# csa_drvio_v1_1a.net
KiCad netlist of a schematic drawn in EAGLE
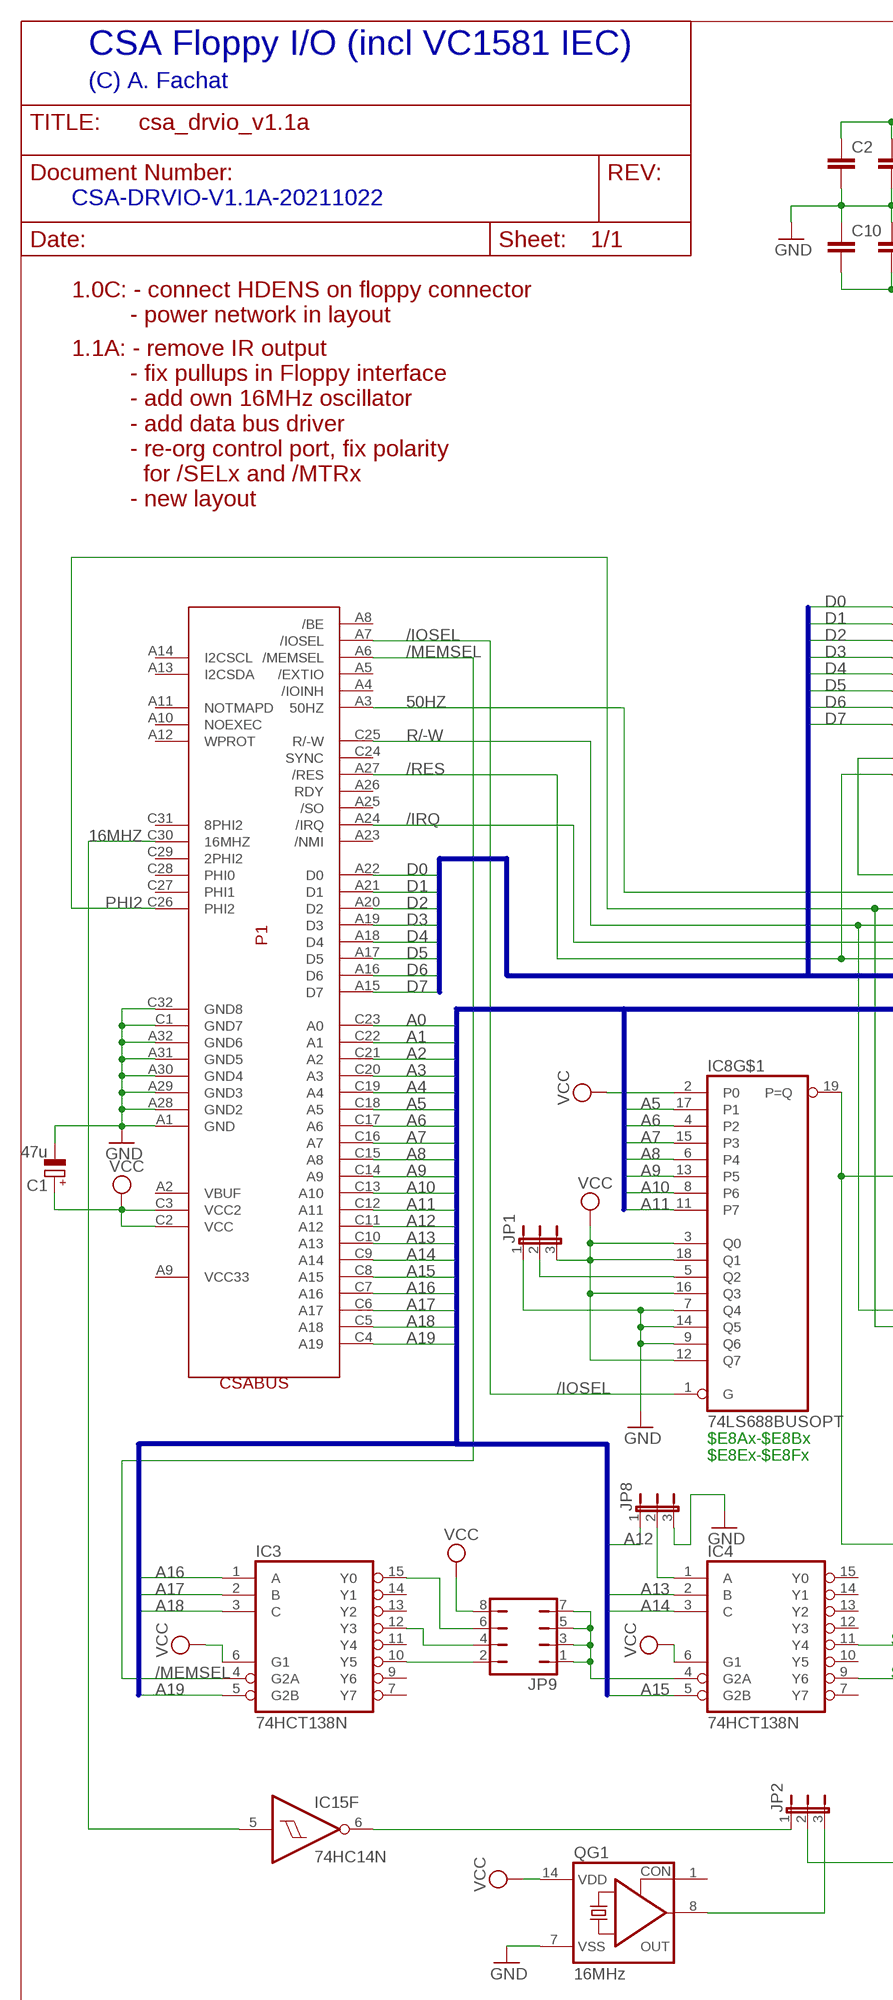
[diagram p0: schematic, sheet 1, part 1 of 2]
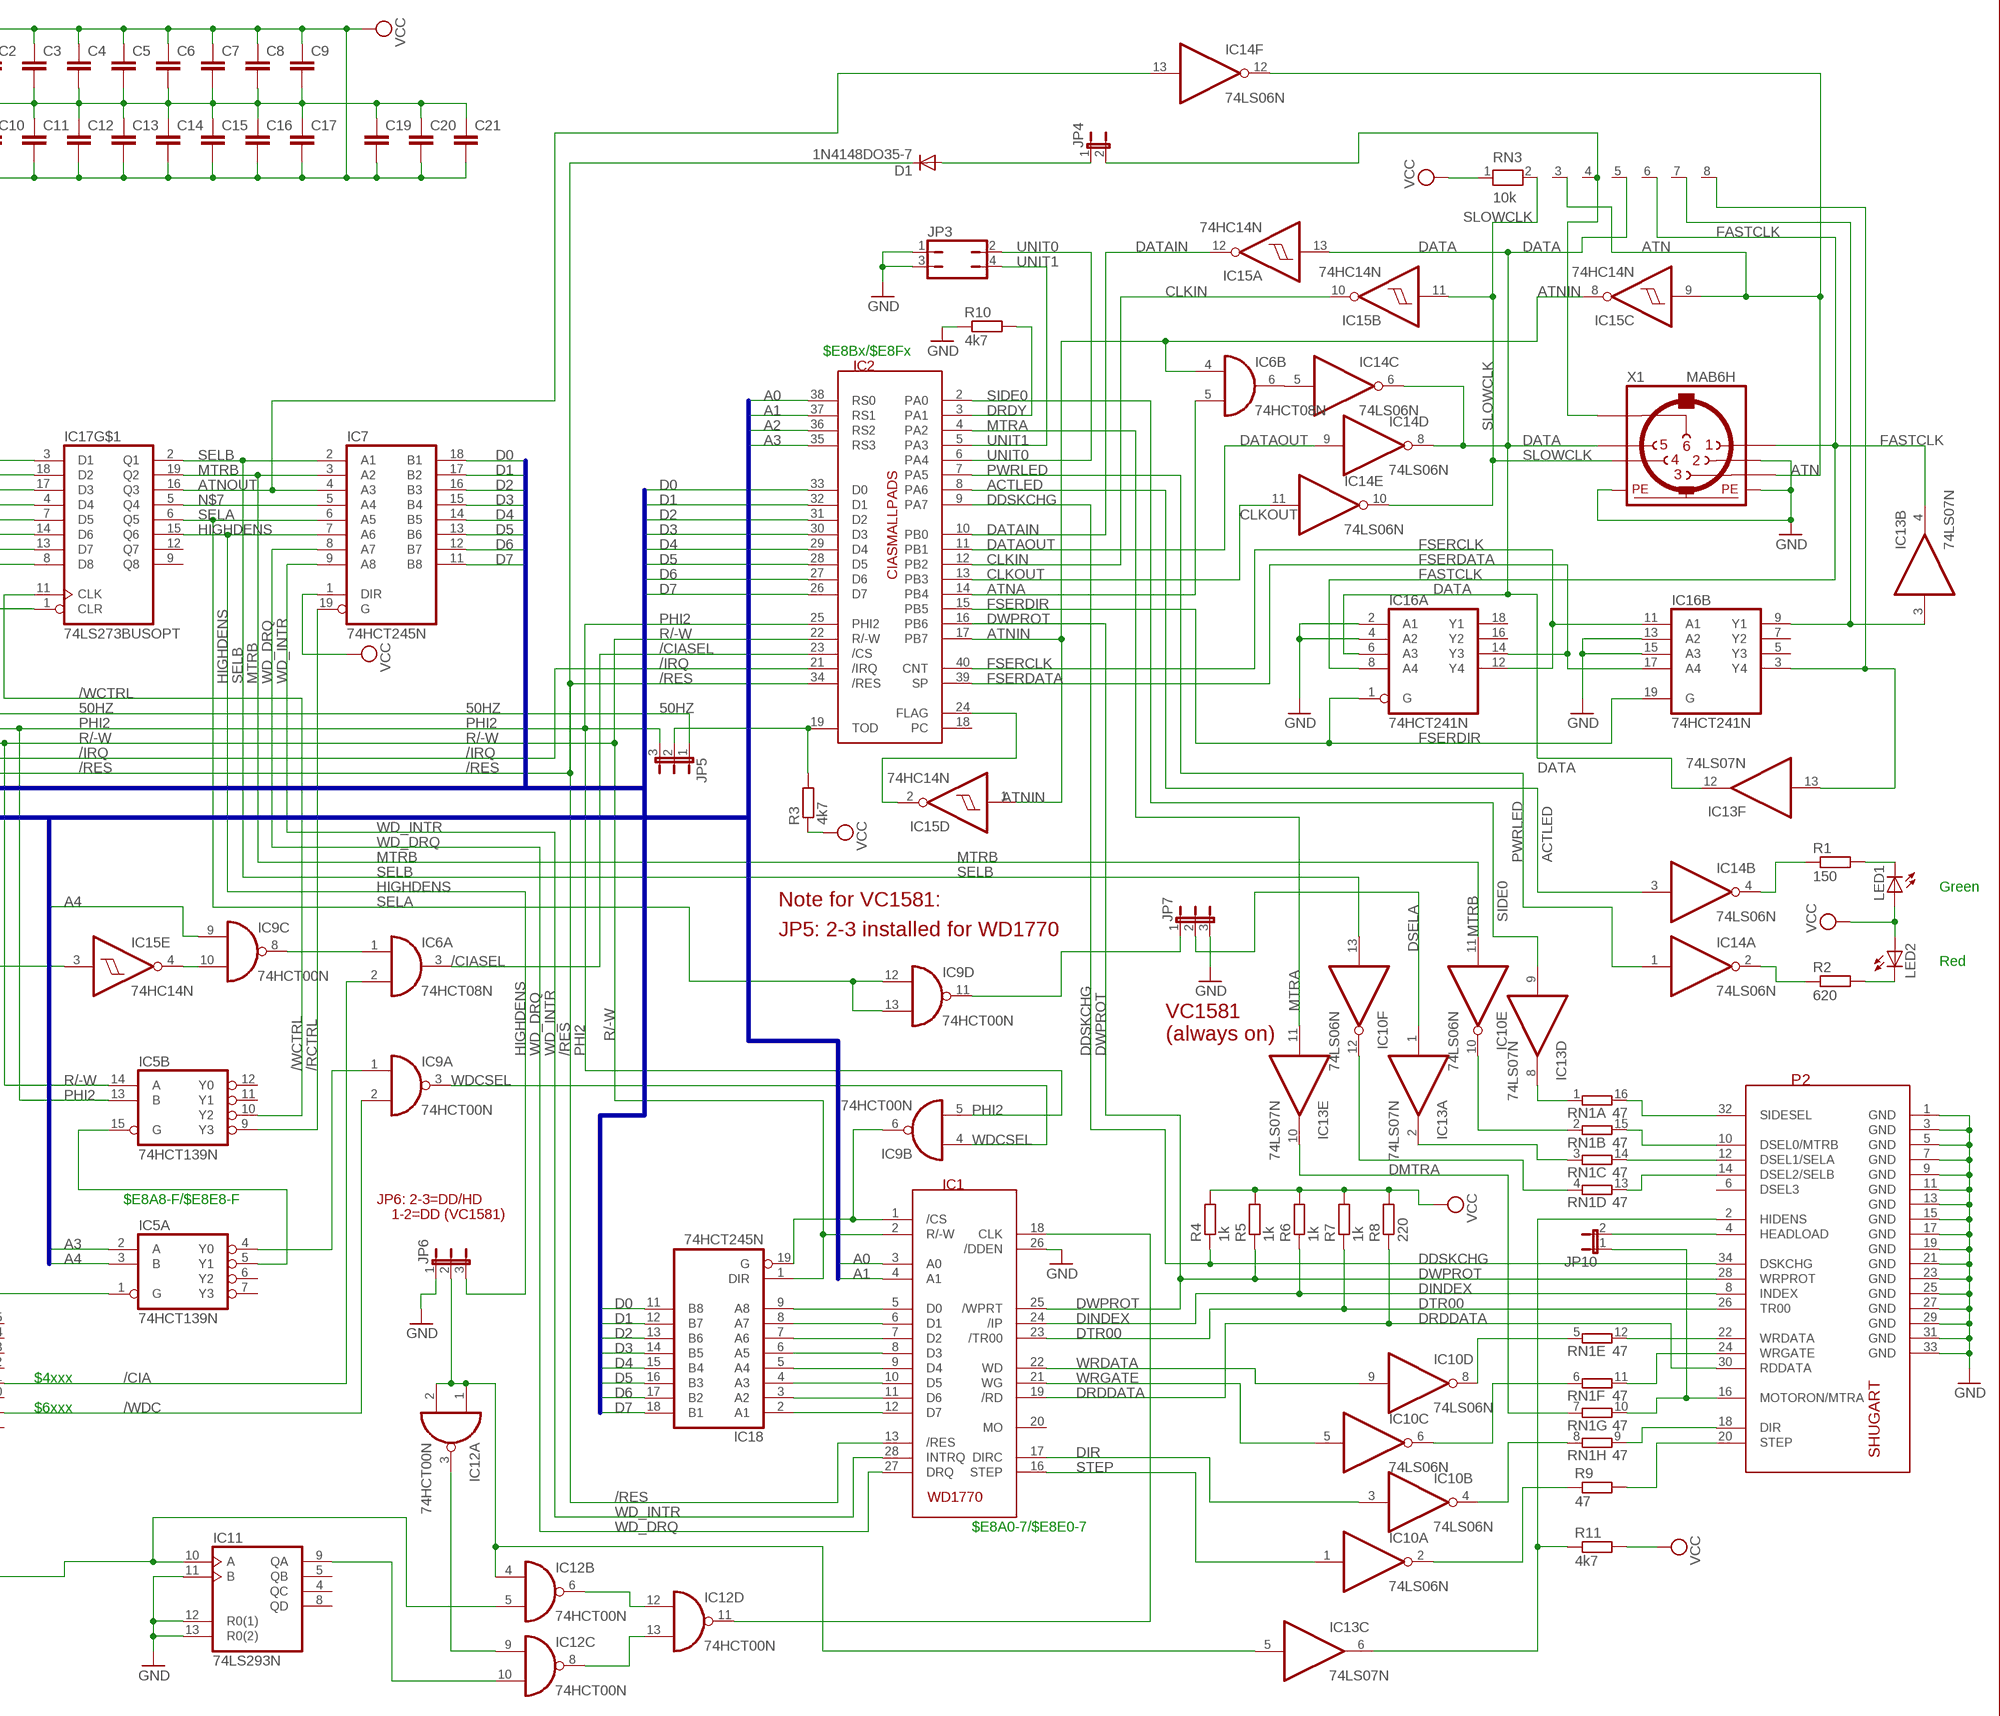
[diagram p1: schematic, sheet 1, part 2 of 2]

(export (version "E")
  (design (tool "Eeschema 10.0.6"))
  (components
    (comp (ref "C1")
      (value "47u")
      (footprint "eagle-import:E2,5-5")
      (libsource (lib "eagle-import") (part "CPOL-EUE2.5-5"))
    )
    (comp (ref "C2")
      (value "C-EU025-025X050")
      (footprint "eagle-import:C025-025X050")
      (libsource (lib "eagle-import") (part "C-EU025-025X050"))
    )
    (comp (ref "C3")
      (value "C-EU025-025X050")
      (footprint "eagle-import:C025-025X050")
      (libsource (lib "eagle-import") (part "C-EU025-025X050"))
    )
    (comp (ref "C4")
      (value "C-EU025-025X050")
      (footprint "eagle-import:C025-025X050")
      (libsource (lib "eagle-import") (part "C-EU025-025X050"))
    )
    (comp (ref "C5")
      (value "C-EU025-025X050")
      (footprint "eagle-import:C025-025X050")
      (libsource (lib "eagle-import") (part "C-EU025-025X050"))
    )
    (comp (ref "C6")
      (value "C-EU025-025X050")
      (footprint "eagle-import:C025-025X050")
      (libsource (lib "eagle-import") (part "C-EU025-025X050"))
    )
    (comp (ref "C7")
      (value "C-EU025-025X050")
      (footprint "eagle-import:C025-025X050")
      (libsource (lib "eagle-import") (part "C-EU025-025X050"))
    )
    (comp (ref "C8")
      (value "C-EU025-025X050")
      (footprint "eagle-import:C025-025X050")
      (libsource (lib "eagle-import") (part "C-EU025-025X050"))
    )
    (comp (ref "C9")
      (value "C-EU025-025X050")
      (footprint "eagle-import:C025-025X050")
      (libsource (lib "eagle-import") (part "C-EU025-025X050"))
    )
    (comp (ref "C10")
      (value "C-EU025-025X050")
      (footprint "eagle-import:C025-025X050")
      (libsource (lib "eagle-import") (part "C-EU025-025X050"))
    )
    (comp (ref "C11")
      (value "C-EU025-025X050")
      (footprint "eagle-import:C025-025X050")
      (libsource (lib "eagle-import") (part "C-EU025-025X050"))
    )
    (comp (ref "C12")
      (value "C-EU025-025X050")
      (footprint "eagle-import:C025-025X050")
      (libsource (lib "eagle-import") (part "C-EU025-025X050"))
    )
    (comp (ref "C13")
      (value "C-EU025-025X050")
      (footprint "eagle-import:C025-025X050")
      (libsource (lib "eagle-import") (part "C-EU025-025X050"))
    )
    (comp (ref "C14")
      (value "C-EU025-025X050")
      (footprint "eagle-import:C025-025X050")
      (libsource (lib "eagle-import") (part "C-EU025-025X050"))
    )
    (comp (ref "C15")
      (value "C-EU025-025X050")
      (footprint "eagle-import:C025-025X050")
      (libsource (lib "eagle-import") (part "C-EU025-025X050"))
    )
    (comp (ref "C16")
      (value "C-EU025-025X050")
      (footprint "eagle-import:C025-025X050")
      (libsource (lib "eagle-import") (part "C-EU025-025X050"))
    )
    (comp (ref "C17")
      (value "C-EU025-025X050")
      (footprint "eagle-import:C025-025X050")
      (libsource (lib "eagle-import") (part "C-EU025-025X050"))
    )
    (comp (ref "C19")
      (value "C-EU025-025X050")
      (footprint "eagle-import:C025-025X050")
      (libsource (lib "eagle-import") (part "C-EU025-025X050"))
    )
    (comp (ref "C20")
      (value "C-EU025-025X050")
      (footprint "eagle-import:C025-025X050")
      (libsource (lib "eagle-import") (part "C-EU025-025X050"))
    )
    (comp (ref "C21")
      (value "C-EU025-025X050")
      (footprint "eagle-import:C025-025X050")
      (libsource (lib "eagle-import") (part "C-EU025-025X050"))
    )
    (comp (ref "D1")
      (value "1N4148DO35-7")
      (footprint "eagle-import:DO35-7")
      (libsource (lib "eagle-import") (part "1N4148DO35-7"))
    )
    (comp (ref "IC1")
      (value "WD1770")
      (footprint "eagle-import:DIL28")
      (libsource (lib "eagle-import") (part "WD1770"))
    )
    (comp (ref "IC2")
      (value "CIASMALLPADS")
      (footprint "eagle-import:DIP40")
      (libsource (lib "eagle-import") (part "CIASMALLPADS"))
    )
    (comp (ref "IC3")
      (value "74HCT138N")
      (footprint "eagle-import:DIL16")
      (libsource (lib "eagle-import") (part "74138NHCT"))
    )
    (comp (ref "IC4")
      (value "74HCT138N")
      (footprint "eagle-import:DIL16")
      (libsource (lib "eagle-import") (part "74138NHCT"))
    )
    (comp (ref "IC5")
      (value "74HCT139N")
      (footprint "eagle-import:DIL16")
      (libsource (lib "eagle-import") (part "74139NHCT"))
    )
    (comp (ref "IC6")
      (value "74HCT08N")
      (footprint "eagle-import:DIL14")
      (libsource (lib "eagle-import") (part "7408NHCT"))
    )
    (comp (ref "IC7")
      (value "74HCT245N")
      (footprint "eagle-import:DIL20")
      (libsource (lib "eagle-import") (part "74245NHCT"))
    )
    (comp (ref "IC8")
      (value "74LS688BUSOPT")
      (footprint "eagle-import:DIL20")
      (libsource (lib "eagle-import") (part "74LS688BUSOPT"))
    )
    (comp (ref "IC9")
      (value "74HCT00N")
      (footprint "eagle-import:DIL14")
      (libsource (lib "eagle-import") (part "7400NHCT"))
    )
    (comp (ref "IC10")
      (value "74LS06N")
      (footprint "eagle-import:DIL14")
      (libsource (lib "eagle-import") (part "7406NLS"))
    )
    (comp (ref "IC11")
      (value "74LS293N")
      (footprint "eagle-import:DIL14")
      (libsource (lib "eagle-import") (part "74293NLS"))
    )
    (comp (ref "IC12")
      (value "74HCT00N")
      (footprint "eagle-import:DIL14")
      (libsource (lib "eagle-import") (part "7400NHCT"))
    )
    (comp (ref "IC13")
      (value "74LS07N")
      (footprint "eagle-import:DIL14")
      (libsource (lib "eagle-import") (part "7407NLS"))
    )
    (comp (ref "IC14")
      (value "74LS06N")
      (footprint "eagle-import:DIL14")
      (libsource (lib "eagle-import") (part "7406NLS"))
    )
    (comp (ref "IC15")
      (value "74HC14N")
      (footprint "eagle-import:DIL14")
      (libsource (lib "eagle-import") (part "7414NHC"))
    )
    (comp (ref "IC16")
      (value "74HCT241N")
      (footprint "eagle-import:DIL20")
      (libsource (lib "eagle-import") (part "74241NHCT"))
    )
    (comp (ref "IC17")
      (value "74LS273BUSOPT")
      (footprint "eagle-import:DIL20")
      (libsource (lib "eagle-import") (part "74LS273BUSOPT"))
    )
    (comp (ref "IC18")
      (value "74HCT245N")
      (footprint "eagle-import:DIL20")
      (libsource (lib "eagle-import") (part "74245NHCT"))
    )
    (comp (ref "JP1")
      (value "JP2E")
      (footprint "eagle-import:JP2")
      (libsource (lib "eagle-import") (part "JP2E"))
    )
    (comp (ref "JP2")
      (value "JP2E")
      (footprint "eagle-import:JP2")
      (libsource (lib "eagle-import") (part "JP2E"))
    )
    (comp (ref "JP3")
      (value "JP2Q")
      (footprint "eagle-import:JP2Q")
      (libsource (lib "eagle-import") (part "JP2Q"))
    )
    (comp (ref "JP4")
      (value "JP1E")
      (footprint "eagle-import:JP1")
      (libsource (lib "eagle-import") (part "JP1E"))
    )
    (comp (ref "JP5")
      (value "JP2E")
      (footprint "eagle-import:JP2")
      (libsource (lib "eagle-import") (part "JP2E"))
    )
    (comp (ref "JP6")
      (value "JP2E")
      (footprint "eagle-import:JP2")
      (libsource (lib "eagle-import") (part "JP2E"))
    )
    (comp (ref "JP7")
      (value "JP2E")
      (footprint "eagle-import:JP2")
      (libsource (lib "eagle-import") (part "JP2E"))
    )
    (comp (ref "JP8")
      (value "JP2E")
      (footprint "eagle-import:JP2")
      (libsource (lib "eagle-import") (part "JP2E"))
    )
    (comp (ref "JP9")
      (value "JP4Q")
      (footprint "eagle-import:JP4Q")
      (libsource (lib "eagle-import") (part "JP4Q"))
    )
    (comp (ref "JP10")
      (value "JP1E")
      (footprint "eagle-import:JP1")
      (libsource (lib "eagle-import") (part "JP1E"))
    )
    (comp (ref "LED1")
      (value "LED5MM")
      (footprint "eagle-import:LED5MM")
      (libsource (lib "eagle-import") (part "LED5MM"))
    )
    (comp (ref "LED2")
      (value "LED5MM")
      (footprint "eagle-import:LED5MM")
      (libsource (lib "eagle-import") (part "LED5MM"))
    )
    (comp (ref "P1")
      (value "CSABUS")
      (footprint "eagle-import:CSABUS")
      (libsource (lib "eagle-import") (part "CSABUS"))
    )
    (comp (ref "P2")
      (value "SHUGART")
      (footprint "eagle-import:CON34")
      (libsource (lib "eagle-import") (part "SHUGART"))
    )
    (comp (ref "QG1")
      (value "16MHz")
      (footprint "eagle-import:SG51")
      (libsource (lib "eagle-import") (part "CRYSTAL_RES-SG51"))
    )
    (comp (ref "R1")
      (value "150")
      (footprint "eagle-import:0207_10")
      (libsource (lib "eagle-import") (part "R-EU_0207/10"))
    )
    (comp (ref "R2")
      (value "620")
      (footprint "eagle-import:0207_10")
      (libsource (lib "eagle-import") (part "R-EU_0207/10"))
    )
    (comp (ref "R3")
      (value "4k7")
      (footprint "eagle-import:0204_7")
      (libsource (lib "eagle-import") (part "R-EU_0204/7"))
    )
    (comp (ref "R4")
      (value "1k")
      (footprint "eagle-import:0207_10")
      (libsource (lib "eagle-import") (part "R-EU_0207/10"))
    )
    (comp (ref "R5")
      (value "1k")
      (footprint "eagle-import:0207_10")
      (libsource (lib "eagle-import") (part "R-EU_0207/10"))
    )
    (comp (ref "R6")
      (value "1k")
      (footprint "eagle-import:0207_10")
      (libsource (lib "eagle-import") (part "R-EU_0207/10"))
    )
    (comp (ref "R7")
      (value "1k")
      (footprint "eagle-import:0207_10")
      (libsource (lib "eagle-import") (part "R-EU_0207/10"))
    )
    (comp (ref "R8")
      (value "220")
      (footprint "eagle-import:0207_10")
      (libsource (lib "eagle-import") (part "R-EU_0207/10"))
    )
    (comp (ref "R9")
      (value "47")
      (footprint "eagle-import:0207_10")
      (libsource (lib "eagle-import") (part "R-EU_0207/10"))
    )
    (comp (ref "R10")
      (value "4k7")
      (footprint "eagle-import:0207_10")
      (libsource (lib "eagle-import") (part "R-EU_0207/10"))
    )
    (comp (ref "R11")
      (value "4k7")
      (footprint "eagle-import:0207_10")
      (libsource (lib "eagle-import") (part "R-EU_0207/10"))
    )
    (comp (ref "RN1")
      (value "47")
      (footprint "eagle-import:DIL16")
      (libsource (lib "eagle-import") (part "8R-N"))
    )
    (comp (ref "RN3")
      (value "10k")
      (footprint "eagle-import:RN-8")
      (libsource (lib "eagle-import") (part "RN07"))
    )
    (comp (ref "X1")
      (value "MAB6H")
      (footprint "eagle-import:MAB6H")
      (libsource (lib "eagle-import") (part "MAB6H"))
    )
  )
  (nets
    (net (code "1") (name "/16MHZ") (class "Default")
      (node (ref "IC15") (pin "5") (pinfunction "I_5") (pintype "input"))
      (node (ref "P1") (pin "C30") (pinfunction "16MHZ_C30") (pintype "bidirectional"))
    )
    (net (code "2") (name "/50HZ") (class "Default")
      (node (ref "JP5") (pin "1") (pinfunction "1_1") (pintype "passive"))
      (node (ref "P1") (pin "A3") (pinfunction "50HZ_A3") (pintype "bidirectional"))
    )
    (net (code "3") (name "/A0") (class "Default")
      (node (ref "IC1") (pin "3") (pinfunction "A0_3") (pintype "bidirectional"))
      (node (ref "IC2") (pin "38") (pinfunction "RS0_38") (pintype "bidirectional"))
      (node (ref "P1") (pin "C23") (pinfunction "A0_C23") (pintype "bidirectional"))
    )
    (net (code "4") (name "/A1") (class "Default")
      (node (ref "IC1") (pin "4") (pinfunction "A1_4") (pintype "bidirectional"))
      (node (ref "IC2") (pin "37") (pinfunction "RS1_37") (pintype "bidirectional"))
      (node (ref "P1") (pin "C22") (pinfunction "A1_C22") (pintype "bidirectional"))
    )
    (net (code "5") (name "/A2") (class "Default")
      (node (ref "IC2") (pin "36") (pinfunction "RS2_36") (pintype "bidirectional"))
      (node (ref "P1") (pin "C21") (pinfunction "A2_C21") (pintype "bidirectional"))
    )
    (net (code "6") (name "/A3") (class "Default")
      (node (ref "IC2") (pin "35") (pinfunction "RS3_35") (pintype "bidirectional"))
      (node (ref "IC5") (pin "2") (pinfunction "A_2") (pintype "input"))
      (node (ref "P1") (pin "C20") (pinfunction "A3_C20") (pintype "bidirectional"))
    )
    (net (code "7") (name "/A4") (class "Default")
      (node (ref "IC5") (pin "3") (pinfunction "B_3") (pintype "input"))
      (node (ref "IC9") (pin "9") (pinfunction "I0_9") (pintype "input"))
      (node (ref "P1") (pin "C19") (pinfunction "A4_C19") (pintype "bidirectional"))
    )
    (net (code "8") (name "/A5") (class "Default")
      (node (ref "IC8") (pin "17") (pinfunction "P1_17") (pintype "input"))
      (node (ref "P1") (pin "C18") (pinfunction "A5_C18") (pintype "bidirectional"))
    )
    (net (code "9") (name "/A6") (class "Default")
      (node (ref "IC8") (pin "4") (pinfunction "P2_4") (pintype "input"))
      (node (ref "P1") (pin "C17") (pinfunction "A6_C17") (pintype "bidirectional"))
    )
    (net (code "10") (name "/A7") (class "Default")
      (node (ref "IC8") (pin "15") (pinfunction "P3_15") (pintype "input"))
      (node (ref "P1") (pin "C16") (pinfunction "A7_C16") (pintype "bidirectional"))
    )
    (net (code "11") (name "/A8") (class "Default")
      (node (ref "IC8") (pin "6") (pinfunction "P4_6") (pintype "input"))
      (node (ref "P1") (pin "C15") (pinfunction "A8_C15") (pintype "bidirectional"))
    )
    (net (code "12") (name "/A9") (class "Default")
      (node (ref "IC8") (pin "13") (pinfunction "P5_13") (pintype "input"))
      (node (ref "P1") (pin "C14") (pinfunction "A9_C14") (pintype "bidirectional"))
    )
    (net (code "13") (name "/A10") (class "Default")
      (node (ref "IC8") (pin "8") (pinfunction "P6_8") (pintype "input"))
      (node (ref "P1") (pin "C13") (pinfunction "A10_C13") (pintype "bidirectional"))
    )
    (net (code "14") (name "/A11") (class "Default")
      (node (ref "IC8") (pin "11") (pinfunction "P7_11") (pintype "input"))
      (node (ref "P1") (pin "C12") (pinfunction "A11_C12") (pintype "bidirectional"))
    )
    (net (code "15") (name "/A12") (class "Default")
      (node (ref "JP8") (pin "1") (pinfunction "1_1") (pintype "passive"))
      (node (ref "P1") (pin "C11") (pinfunction "A12_C11") (pintype "bidirectional"))
    )
    (net (code "16") (name "/A13") (class "Default")
      (node (ref "IC4") (pin "2") (pinfunction "B_2") (pintype "input"))
      (node (ref "P1") (pin "C10") (pinfunction "A13_C10") (pintype "bidirectional"))
    )
    (net (code "17") (name "/A14") (class "Default")
      (node (ref "IC4") (pin "3") (pinfunction "C_3") (pintype "input"))
      (node (ref "P1") (pin "C9") (pinfunction "A14_C9") (pintype "bidirectional"))
    )
    (net (code "18") (name "/A15") (class "Default")
      (node (ref "IC4") (pin "5") (pinfunction "G2B_5") (pintype "input"))
      (node (ref "P1") (pin "C8") (pinfunction "A15_C8") (pintype "bidirectional"))
    )
    (net (code "19") (name "/A16") (class "Default")
      (node (ref "IC3") (pin "1") (pinfunction "A_1") (pintype "input"))
      (node (ref "P1") (pin "C7") (pinfunction "A16_C7") (pintype "bidirectional"))
    )
    (net (code "20") (name "/A17") (class "Default")
      (node (ref "IC3") (pin "2") (pinfunction "B_2") (pintype "input"))
      (node (ref "P1") (pin "C6") (pinfunction "A17_C6") (pintype "bidirectional"))
    )
    (net (code "21") (name "/A18") (class "Default")
      (node (ref "IC3") (pin "3") (pinfunction "C_3") (pintype "input"))
      (node (ref "P1") (pin "C5") (pinfunction "A18_C5") (pintype "bidirectional"))
    )
    (net (code "22") (name "/A19") (class "Default")
      (node (ref "IC3") (pin "5") (pinfunction "G2B_5") (pintype "input"))
      (node (ref "P1") (pin "C4") (pinfunction "A19_C4") (pintype "bidirectional"))
    )
    (net (code "23") (name "/ACTLED") (class "Default")
      (node (ref "IC14") (pin "3") (pinfunction "I_3") (pintype "input"))
      (node (ref "IC2") (pin "8") (pinfunction "PA6_8") (pintype "bidirectional"))
    )
    (net (code "24") (name "/ATN") (class "Default")
      (node (ref "IC14") (pin "12") (pinfunction "O_12") (pintype "open_collector"))
      (node (ref "IC15") (pin "9") (pinfunction "I_9") (pintype "input"))
      (node (ref "RN3") (pin "3") (pinfunction "3_3") (pintype "passive"))
      (node (ref "X1") (pin "3") (pinfunction "3_3") (pintype "passive"))
    )
    (net (code "25") (name "/ATNA") (class "Default")
      (node (ref "IC2") (pin "14") (pinfunction "PB4_14") (pintype "bidirectional"))
      (node (ref "IC6") (pin "5") (pinfunction "I1_5") (pintype "input"))
    )
    (net (code "26") (name "/ATNIN") (class "Default")
      (node (ref "IC15") (pin "1") (pinfunction "I_1") (pintype "input"))
      (node (ref "IC15") (pin "8") (pinfunction "O_8") (pintype "output"))
      (node (ref "IC2") (pin "17") (pinfunction "PB7_17") (pintype "bidirectional"))
      (node (ref "IC6") (pin "4") (pinfunction "I0_4") (pintype "input"))
    )
    (net (code "27") (name "/ATNOUT") (class "Default")
      (node (ref "IC14") (pin "13") (pinfunction "I_13") (pintype "input"))
      (node (ref "IC17") (pin "16") (pinfunction "Q3_16") (pintype "output"))
      (node (ref "IC7") (pin "4") (pinfunction "A3_4") (pintype "bidirectional"))
    )
    (net (code "28") (name "/CLKIN") (class "Default")
      (node (ref "IC15") (pin "10") (pinfunction "O_10") (pintype "output"))
      (node (ref "IC2") (pin "12") (pinfunction "PB2_12") (pintype "bidirectional"))
    )
    (net (code "29") (name "/CLKOUT") (class "Default")
      (node (ref "IC14") (pin "11") (pinfunction "I_11") (pintype "input"))
      (node (ref "IC2") (pin "13") (pinfunction "PB3_13") (pintype "bidirectional"))
    )
    (net (code "30") (name "/D0") (class "Default")
      (node (ref "IC17") (pin "3") (pinfunction "D1_3") (pintype "input"))
      (node (ref "IC18") (pin "11") (pinfunction "B8_11") (pintype "bidirectional"))
      (node (ref "IC2") (pin "33") (pinfunction "D0_33") (pintype "bidirectional"))
      (node (ref "IC7") (pin "18") (pinfunction "B1_18") (pintype "bidirectional"))
      (node (ref "P1") (pin "A22") (pinfunction "D0_A22") (pintype "bidirectional"))
    )
    (net (code "31") (name "/D1") (class "Default")
      (node (ref "IC17") (pin "18") (pinfunction "D2_18") (pintype "input"))
      (node (ref "IC18") (pin "12") (pinfunction "B7_12") (pintype "bidirectional"))
      (node (ref "IC2") (pin "32") (pinfunction "D1_32") (pintype "bidirectional"))
      (node (ref "IC7") (pin "17") (pinfunction "B2_17") (pintype "bidirectional"))
      (node (ref "P1") (pin "A21") (pinfunction "D1_A21") (pintype "bidirectional"))
    )
    (net (code "32") (name "/D2") (class "Default")
      (node (ref "IC17") (pin "17") (pinfunction "D3_17") (pintype "input"))
      (node (ref "IC18") (pin "13") (pinfunction "B6_13") (pintype "bidirectional"))
      (node (ref "IC2") (pin "31") (pinfunction "D2_31") (pintype "bidirectional"))
      (node (ref "IC7") (pin "16") (pinfunction "B3_16") (pintype "bidirectional"))
      (node (ref "P1") (pin "A20") (pinfunction "D2_A20") (pintype "bidirectional"))
    )
    (net (code "33") (name "/D3") (class "Default")
      (node (ref "IC17") (pin "4") (pinfunction "D4_4") (pintype "input"))
      (node (ref "IC18") (pin "14") (pinfunction "B5_14") (pintype "bidirectional"))
      (node (ref "IC2") (pin "30") (pinfunction "D3_30") (pintype "bidirectional"))
      (node (ref "IC7") (pin "15") (pinfunction "B4_15") (pintype "bidirectional"))
      (node (ref "P1") (pin "A19") (pinfunction "D3_A19") (pintype "bidirectional"))
    )
    (net (code "34") (name "/D4") (class "Default")
      (node (ref "IC17") (pin "7") (pinfunction "D5_7") (pintype "input"))
      (node (ref "IC18") (pin "15") (pinfunction "B4_15") (pintype "bidirectional"))
      (node (ref "IC2") (pin "29") (pinfunction "D4_29") (pintype "bidirectional"))
      (node (ref "IC7") (pin "14") (pinfunction "B5_14") (pintype "bidirectional"))
      (node (ref "P1") (pin "A18") (pinfunction "D4_A18") (pintype "bidirectional"))
    )
    (net (code "35") (name "/D5") (class "Default")
      (node (ref "IC17") (pin "14") (pinfunction "D6_14") (pintype "input"))
      (node (ref "IC18") (pin "16") (pinfunction "B3_16") (pintype "bidirectional"))
      (node (ref "IC2") (pin "28") (pinfunction "D5_28") (pintype "bidirectional"))
      (node (ref "IC7") (pin "13") (pinfunction "B6_13") (pintype "bidirectional"))
      (node (ref "P1") (pin "A17") (pinfunction "D5_A17") (pintype "bidirectional"))
    )
    (net (code "36") (name "/D6") (class "Default")
      (node (ref "IC17") (pin "13") (pinfunction "D7_13") (pintype "input"))
      (node (ref "IC18") (pin "17") (pinfunction "B2_17") (pintype "bidirectional"))
      (node (ref "IC2") (pin "27") (pinfunction "D6_27") (pintype "bidirectional"))
      (node (ref "IC7") (pin "12") (pinfunction "B7_12") (pintype "bidirectional"))
      (node (ref "P1") (pin "A16") (pinfunction "D6_A16") (pintype "bidirectional"))
    )
    (net (code "37") (name "/D7") (class "Default")
      (node (ref "IC17") (pin "8") (pinfunction "D8_8") (pintype "input"))
      (node (ref "IC18") (pin "18") (pinfunction "B1_18") (pintype "bidirectional"))
      (node (ref "IC2") (pin "26") (pinfunction "D7_26") (pintype "bidirectional"))
      (node (ref "IC7") (pin "11") (pinfunction "B8_11") (pintype "bidirectional"))
      (node (ref "P1") (pin "A15") (pinfunction "D7_A15") (pintype "bidirectional"))
    )
    (net (code "38") (name "/DATA") (class "Default")
      (node (ref "IC13") (pin "12") (pinfunction "O_12") (pintype "open_collector"))
      (node (ref "IC14") (pin "6") (pinfunction "O_6") (pintype "open_collector"))
      (node (ref "IC14") (pin "8") (pinfunction "O_8") (pintype "open_collector"))
      (node (ref "IC15") (pin "13") (pinfunction "I_13") (pintype "input"))
      (node (ref "IC16") (pin "6") (pinfunction "A3_6") (pintype "input"))
      (node (ref "RN3") (pin "5") (pinfunction "5_5") (pintype "passive"))
      (node (ref "X1") (pin "5") (pinfunction "5_5") (pintype "passive"))
    )
    (net (code "39") (name "/DATAIN") (class "Default")
      (node (ref "IC15") (pin "12") (pinfunction "O_12") (pintype "output"))
      (node (ref "IC2") (pin "10") (pinfunction "PB0_10") (pintype "bidirectional"))
    )
    (net (code "40") (name "/DATAOUT") (class "Default")
      (node (ref "IC14") (pin "9") (pinfunction "I_9") (pintype "input"))
      (node (ref "IC2") (pin "11") (pinfunction "PB1_11") (pintype "bidirectional"))
    )
    (net (code "41") (name "/DDSKCHG") (class "Default")
      (node (ref "IC2") (pin "9") (pinfunction "PA7_9") (pintype "bidirectional"))
      (node (ref "P2") (pin "34") (pinfunction "DSKCHG_34") (pintype "output"))
      (node (ref "R4") (pin "1") (pinfunction "1_1") (pintype "passive"))
    )
    (net (code "42") (name "/DINDEX") (class "Default")
      (node (ref "IC1") (pin "24") (pinfunction "/IP_24") (pintype "bidirectional"))
      (node (ref "P2") (pin "8") (pinfunction "INDEX_8") (pintype "output"))
      (node (ref "R6") (pin "1") (pinfunction "1_1") (pintype "passive"))
    )
    (net (code "43") (name "/DIR") (class "Default")
      (node (ref "IC1") (pin "17") (pinfunction "DIRC_17") (pintype "bidirectional"))
      (node (ref "IC10") (pin "3") (pinfunction "I_3") (pintype "input"))
    )
    (net (code "44") (name "/DMTRA") (class "Default")
      (node (ref "IC13") (pin "10") (pinfunction "O_10") (pintype "open_collector"))
      (node (ref "RN1") (pin "7") (pinfunction "1_7") (pintype "passive"))
    )
    (net (code "45") (name "/DRDDATA") (class "Default")
      (node (ref "IC1") (pin "19") (pinfunction "/RD_19") (pintype "bidirectional"))
      (node (ref "P2") (pin "30") (pinfunction "RDDATA_30") (pintype "output"))
      (node (ref "R8") (pin "1") (pinfunction "1_1") (pintype "passive"))
    )
    (net (code "46") (name "/DRDY") (class "Default")
      (node (ref "IC2") (pin "3") (pinfunction "PA1_3") (pintype "bidirectional"))
      (node (ref "R10") (pin "2") (pinfunction "2_2") (pintype "passive"))
    )
    (net (code "47") (name "/DSELA") (class "Default")
      (node (ref "IC13") (pin "1") (pinfunction "I_1") (pintype "input"))
      (node (ref "JP7") (pin "2") (pinfunction "2_2") (pintype "passive"))
    )
    (net (code "48") (name "/DTR00") (class "Default")
      (node (ref "IC1") (pin "23") (pinfunction "/TR00_23") (pintype "bidirectional"))
      (node (ref "P2") (pin "26") (pinfunction "TR00_26") (pintype "output"))
      (node (ref "R7") (pin "1") (pinfunction "1_1") (pintype "passive"))
    )
    (net (code "49") (name "/DWPROT") (class "Default")
      (node (ref "IC1") (pin "25") (pinfunction "/WPRT_25") (pintype "bidirectional"))
      (node (ref "IC2") (pin "16") (pinfunction "PB6_16") (pintype "bidirectional"))
      (node (ref "P2") (pin "28") (pinfunction "WRPROT_28") (pintype "output"))
      (node (ref "R5") (pin "1") (pinfunction "1_1") (pintype "passive"))
    )
    (net (code "50") (name "/FASTCLK") (class "Default")
      (node (ref "IC13") (pin "4") (pinfunction "O_4") (pintype "open_collector"))
      (node (ref "IC16") (pin "8") (pinfunction "A4_8") (pintype "input"))
      (node (ref "RN3") (pin "6") (pinfunction "6_6") (pintype "passive"))
      (node (ref "X1") (pin "1") (pinfunction "1_1") (pintype "passive"))
    )
    (net (code "51") (name "/FSERCLK") (class "Default")
      (node (ref "IC16") (pin "11") (pinfunction "A1_11") (pintype "input"))
      (node (ref "IC16") (pin "12") (pinfunction "Y4_12") (pintype "tri_state"))
      (node (ref "IC2") (pin "40") (pinfunction "CNT_40") (pintype "bidirectional"))
    )
    (net (code "52") (name "/FSERDATA") (class "Default")
      (node (ref "IC16") (pin "14") (pinfunction "Y3_14") (pintype "tri_state"))
      (node (ref "IC16") (pin "17") (pinfunction "A4_17") (pintype "input"))
      (node (ref "IC2") (pin "39") (pinfunction "SP_39") (pintype "bidirectional"))
    )
    (net (code "53") (name "/FSERDIR") (class "Default")
      (node (ref "IC16") (pin "1") (pinfunction "G_1") (pintype "input"))
      (node (ref "IC16") (pin "19") (pinfunction "G_19") (pintype "input"))
      (node (ref "IC2") (pin "15") (pinfunction "PB5_15") (pintype "bidirectional"))
    )
    (net (code "54") (name "/HIGHDENS") (class "Default")
      (node (ref "IC17") (pin "15") (pinfunction "Q6_15") (pintype "output"))
      (node (ref "IC7") (pin "7") (pinfunction "A6_7") (pintype "bidirectional"))
      (node (ref "JP6") (pin "3") (pinfunction "3_3") (pintype "passive"))
    )
    (net (code "55") (name "/MTRA") (class "Default")
      (node (ref "IC13") (pin "11") (pinfunction "I_11") (pintype "input"))
      (node (ref "IC2") (pin "4") (pinfunction "PA2_4") (pintype "bidirectional"))
    )
    (net (code "56") (name "/MTRB") (class "Default")
      (node (ref "IC10") (pin "11") (pinfunction "I_11") (pintype "input"))
      (node (ref "IC17") (pin "19") (pinfunction "Q2_19") (pintype "output"))
      (node (ref "IC7") (pin "3") (pinfunction "A2_3") (pintype "bidirectional"))
    )
    (net (code "57") (name "/N$7") (class "Default")
      (node (ref "IC17") (pin "5") (pinfunction "Q4_5") (pintype "output"))
      (node (ref "IC7") (pin "5") (pinfunction "A4_5") (pintype "bidirectional"))
    )
    (net (code "58") (name "/PHI2") (class "Default")
      (node (ref "IC2") (pin "25") (pinfunction "PHI2_25") (pintype "bidirectional"))
      (node (ref "IC5") (pin "13") (pinfunction "B_13") (pintype "input"))
      (node (ref "IC9") (pin "5") (pinfunction "I1_5") (pintype "input"))
      (node (ref "JP5") (pin "3") (pinfunction "3_3") (pintype "passive"))
      (node (ref "P1") (pin "C26") (pinfunction "PHI2_C26") (pintype "bidirectional"))
    )
    (net (code "59") (name "/PWRLED") (class "Default")
      (node (ref "IC14") (pin "1") (pinfunction "I_1") (pintype "input"))
      (node (ref "IC2") (pin "7") (pinfunction "PA5_7") (pintype "bidirectional"))
    )
    (net (code "60") (name "/R{slash}-W") (class "Default")
      (node (ref "IC1") (pin "2") (pinfunction "R/-W_2") (pintype "bidirectional"))
      (node (ref "IC18") (pin "1") (pinfunction "DIR_1") (pintype "input"))
      (node (ref "IC2") (pin "22") (pinfunction "R/-W_22") (pintype "bidirectional"))
      (node (ref "IC5") (pin "14") (pinfunction "A_14") (pintype "input"))
      (node (ref "P1") (pin "C25") (pinfunction "R/-W_C25") (pintype "bidirectional"))
    )
    (net (code "61") (name "/SELA") (class "Default")
      (node (ref "IC17") (pin "6") (pinfunction "Q5_6") (pintype "output"))
      (node (ref "IC7") (pin "6") (pinfunction "A5_6") (pintype "bidirectional"))
      (node (ref "IC9") (pin "12") (pinfunction "I0_12") (pintype "input"))
      (node (ref "IC9") (pin "13") (pinfunction "I1_13") (pintype "input"))
    )
    (net (code "62") (name "/SELB") (class "Default")
      (node (ref "IC10") (pin "13") (pinfunction "I_13") (pintype "input"))
      (node (ref "IC17") (pin "2") (pinfunction "Q1_2") (pintype "output"))
      (node (ref "IC7") (pin "2") (pinfunction "A1_2") (pintype "bidirectional"))
    )
    (net (code "63") (name "/SIDE0") (class "Default")
      (node (ref "IC13") (pin "9") (pinfunction "I_9") (pintype "input"))
      (node (ref "IC2") (pin "2") (pinfunction "PA0_2") (pintype "bidirectional"))
    )
    (net (code "64") (name "/SLOWCLK") (class "Default")
      (node (ref "IC14") (pin "10") (pinfunction "O_10") (pintype "open_collector"))
      (node (ref "IC15") (pin "11") (pinfunction "I_11") (pintype "input"))
      (node (ref "RN3") (pin "2") (pinfunction "2_2") (pintype "passive"))
      (node (ref "X1") (pin "4") (pinfunction "4_4") (pintype "passive"))
    )
    (net (code "65") (name "/STEP") (class "Default")
      (node (ref "IC1") (pin "16") (pinfunction "STEP_16") (pintype "bidirectional"))
      (node (ref "IC10") (pin "1") (pinfunction "I_1") (pintype "input"))
    )
    (net (code "66") (name "/UNIT0") (class "Default")
      (node (ref "IC2") (pin "6") (pinfunction "PA4_6") (pintype "bidirectional"))
      (node (ref "JP3") (pin "2") (pinfunction "2_2") (pintype "passive"))
    )
    (net (code "67") (name "/UNIT1") (class "Default")
      (node (ref "IC2") (pin "5") (pinfunction "PA3_5") (pintype "bidirectional"))
      (node (ref "JP3") (pin "4") (pinfunction "4_4") (pintype "passive"))
    )
    (net (code "68") (name "/WDCSEL") (class "Default")
      (node (ref "IC9") (pin "3") (pinfunction "O_3") (pintype "output"))
      (node (ref "IC9") (pin "4") (pinfunction "I0_4") (pintype "input"))
    )
    (net (code "69") (name "/WD_DRQ") (class "Default")
      (node (ref "IC1") (pin "27") (pinfunction "DRQ_27") (pintype "bidirectional"))
      (node (ref "IC7") (pin "8") (pinfunction "A7_8") (pintype "bidirectional"))
    )
    (net (code "70") (name "/WD_INTR") (class "Default")
      (node (ref "IC1") (pin "28") (pinfunction "INTRQ_28") (pintype "bidirectional"))
      (node (ref "IC7") (pin "9") (pinfunction "A8_9") (pintype "bidirectional"))
    )
    (net (code "71") (name "/WRDATA") (class "Default")
      (node (ref "IC1") (pin "22") (pinfunction "WD_22") (pintype "bidirectional"))
      (node (ref "IC10") (pin "9") (pinfunction "I_9") (pintype "input"))
    )
    (net (code "72") (name "/WRGATE") (class "Default")
      (node (ref "IC1") (pin "21") (pinfunction "WG_21") (pintype "bidirectional"))
      (node (ref "IC10") (pin "5") (pinfunction "I_5") (pintype "input"))
    )
    (net (code "73") (name "/{slash}CIA") (class "Default")
      (node (ref "IC4") (pin "11") (pinfunction "Y4_11") (pintype "output"))
      (node (ref "IC6") (pin "2") (pinfunction "I1_2") (pintype "input"))
    )
    (net (code "74") (name "/{slash}CIASEL") (class "Default")
      (node (ref "IC2") (pin "23") (pinfunction "/CS_23") (pintype "bidirectional"))
      (node (ref "IC6") (pin "3") (pinfunction "O_3") (pintype "output"))
    )
    (net (code "75") (name "/{slash}IOSEL") (class "Default")
      (node (ref "IC8") (pin "1") (pinfunction "G_1") (pintype "input"))
      (node (ref "P1") (pin "A7") (pinfunction "/IOSEL_A7") (pintype "bidirectional"))
    )
    (net (code "76") (name "/{slash}IRQ") (class "Default")
      (node (ref "IC2") (pin "21") (pinfunction "/IRQ_21") (pintype "bidirectional"))
      (node (ref "P1") (pin "A24") (pinfunction "/IRQ_A24") (pintype "bidirectional"))
    )
    (net (code "77") (name "/{slash}MEMSEL") (class "Default")
      (node (ref "IC3") (pin "4") (pinfunction "G2A_4") (pintype "input"))
      (node (ref "P1") (pin "A6") (pinfunction "/MEMSEL_A6") (pintype "bidirectional"))
    )
    (net (code "78") (name "/{slash}RCTRL") (class "Default")
      (node (ref "IC5") (pin "9") (pinfunction "Y3_9") (pintype "output"))
      (node (ref "IC7") (pin "19") (pinfunction "G_19") (pintype "input"))
    )
    (net (code "79") (name "/{slash}RES") (class "Default")
      (node (ref "D1") (pin "C") (pinfunction "C_C") (pintype "passive"))
      (node (ref "IC1") (pin "13") (pinfunction "/RES_13") (pintype "bidirectional"))
      (node (ref "IC17") (pin "1") (pinfunction "CLR_1") (pintype "input"))
      (node (ref "IC2") (pin "34") (pinfunction "/RES_34") (pintype "bidirectional"))
      (node (ref "P1") (pin "A27") (pinfunction "/RES_A27") (pintype "bidirectional"))
    )
    (net (code "80") (name "/{slash}WCTRL") (class "Default")
      (node (ref "IC17") (pin "11") (pinfunction "CLK_11") (pintype "input"))
      (node (ref "IC5") (pin "10") (pinfunction "Y2_10") (pintype "output"))
    )
    (net (code "81") (name "/{slash}WDC") (class "Default")
      (node (ref "IC4") (pin "9") (pinfunction "Y6_9") (pintype "output"))
      (node (ref "IC9") (pin "2") (pinfunction "I1_2") (pintype "input"))
    )
    (net (code "82") (name "GND") (class "Default")
      (node (ref "C1") (pin "-") (pinfunction "-_-") (pintype "passive"))
      (node (ref "C10") (pin "1") (pinfunction "1_1") (pintype "passive"))
      (node (ref "C11") (pin "1") (pinfunction "1_1") (pintype "passive"))
      (node (ref "C12") (pin "1") (pinfunction "1_1") (pintype "passive"))
      (node (ref "C13") (pin "1") (pinfunction "1_1") (pintype "passive"))
      (node (ref "C14") (pin "1") (pinfunction "1_1") (pintype "passive"))
      (node (ref "C15") (pin "1") (pinfunction "1_1") (pintype "passive"))
      (node (ref "C16") (pin "1") (pinfunction "1_1") (pintype "passive"))
      (node (ref "C17") (pin "1") (pinfunction "1_1") (pintype "passive"))
      (node (ref "C19") (pin "1") (pinfunction "1_1") (pintype "passive"))
      (node (ref "C2") (pin "2") (pinfunction "2_2") (pintype "passive"))
      (node (ref "C20") (pin "1") (pinfunction "1_1") (pintype "passive"))
      (node (ref "C21") (pin "1") (pinfunction "1_1") (pintype "passive"))
      (node (ref "C3") (pin "2") (pinfunction "2_2") (pintype "passive"))
      (node (ref "C4") (pin "2") (pinfunction "2_2") (pintype "passive"))
      (node (ref "C5") (pin "2") (pinfunction "2_2") (pintype "passive"))
      (node (ref "C6") (pin "2") (pinfunction "2_2") (pintype "passive"))
      (node (ref "C7") (pin "2") (pinfunction "2_2") (pintype "passive"))
      (node (ref "C8") (pin "2") (pinfunction "2_2") (pintype "passive"))
      (node (ref "C9") (pin "2") (pinfunction "2_2") (pintype "passive"))
      (node (ref "IC1") (pin "26") (pinfunction "/DDEN_26") (pintype "bidirectional"))
      (node (ref "IC11") (pin "11") (pinfunction "B_11") (pintype "input"))
      (node (ref "IC11") (pin "12") (pinfunction "R0(1)_12") (pintype "input"))
      (node (ref "IC11") (pin "13") (pinfunction "R0(2)_13") (pintype "input"))
      (node (ref "IC16") (pin "13") (pinfunction "A2_13") (pintype "input"))
      (node (ref "IC16") (pin "15") (pinfunction "A3_15") (pintype "input"))
      (node (ref "IC16") (pin "2") (pinfunction "A1_2") (pintype "input"))
      (node (ref "IC16") (pin "4") (pinfunction "A2_4") (pintype "input"))
      (node (ref "IC8") (pin "14") (pinfunction "Q5_14") (pintype "input"))
      (node (ref "IC8") (pin "7") (pinfunction "Q4_7") (pintype "input"))
      (node (ref "IC8") (pin "9") (pinfunction "Q6_9") (pintype "input"))
      (node (ref "JP1") (pin "1") (pinfunction "1_1") (pintype "passive"))
      (node (ref "JP3") (pin "1") (pinfunction "1_1") (pintype "passive"))
      (node (ref "JP3") (pin "3") (pinfunction "3_3") (pintype "passive"))
      (node (ref "JP6") (pin "1") (pinfunction "1_1") (pintype "passive"))
      (node (ref "JP7") (pin "3") (pinfunction "3_3") (pintype "passive"))
      (node (ref "JP8") (pin "3") (pinfunction "3_3") (pintype "passive"))
      (node (ref "P1") (pin "A1") (pinfunction "GND_A1") (pintype "bidirectional"))
      (node (ref "P1") (pin "A28") (pinfunction "GND2_A28") (pintype "bidirectional"))
      (node (ref "P1") (pin "A29") (pinfunction "GND3_A29") (pintype "bidirectional"))
      (node (ref "P1") (pin "A30") (pinfunction "GND4_A30") (pintype "bidirectional"))
      (node (ref "P1") (pin "A31") (pinfunction "GND5_A31") (pintype "bidirectional"))
      (node (ref "P1") (pin "A32") (pinfunction "GND6_A32") (pintype "bidirectional"))
      (node (ref "P1") (pin "C1") (pinfunction "GND7_C1") (pintype "bidirectional"))
      (node (ref "P1") (pin "C32") (pinfunction "GND8_C32") (pintype "bidirectional"))
      (node (ref "P2") (pin "1") (pinfunction "GND_1") (pintype "power_in"))
      (node (ref "P2") (pin "11") (pinfunction "GND_11") (pintype "power_in"))
      (node (ref "P2") (pin "13") (pinfunction "GND_13") (pintype "power_in"))
      (node (ref "P2") (pin "15") (pinfunction "GND_15") (pintype "power_in"))
      (node (ref "P2") (pin "17") (pinfunction "GND_17") (pintype "power_in"))
      (node (ref "P2") (pin "19") (pinfunction "GND_19") (pintype "power_in"))
      (node (ref "P2") (pin "21") (pinfunction "GND_21") (pintype "power_in"))
      (node (ref "P2") (pin "23") (pinfunction "GND_23") (pintype "power_in"))
      (node (ref "P2") (pin "25") (pinfunction "GND_25") (pintype "power_in"))
      (node (ref "P2") (pin "27") (pinfunction "GND_27") (pintype "power_in"))
      (node (ref "P2") (pin "29") (pinfunction "GND_29") (pintype "power_in"))
      (node (ref "P2") (pin "3") (pinfunction "GND_3") (pintype "power_in"))
      (node (ref "P2") (pin "31") (pinfunction "GND_31") (pintype "power_in"))
      (node (ref "P2") (pin "33") (pinfunction "GND_33") (pintype "power_in"))
      (node (ref "P2") (pin "5") (pinfunction "GND_5") (pintype "power_in"))
      (node (ref "P2") (pin "7") (pinfunction "GND_7") (pintype "power_in"))
      (node (ref "P2") (pin "9") (pinfunction "GND_9") (pintype "power_in"))
      (node (ref "QG1") (pin "7") (pinfunction "VSS_7") (pintype "power_in"))
      (node (ref "R10") (pin "1") (pinfunction "1_1") (pintype "passive"))
      (node (ref "X1") (pin "2") (pinfunction "2_2") (pintype "passive"))
      (node (ref "X1") (pin "PE") (pinfunction "PE_PE") (pintype "power_in"))
      (node (ref "X1") (pin "PE@") (pinfunction "PE_PE@") (pintype "power_in"))
    )
    (net (code "83") (name "Net-(D1-PadA)") (class "Default")
      (node (ref "D1") (pin "A") (pinfunction "A_A") (pintype "passive"))
      (node (ref "JP4") (pin "1") (pinfunction "1_1") (pintype "passive"))
    )
    (net (code "84") (name "Net-(IC2A-TOD)") (class "Default")
      (node (ref "IC2") (pin "19") (pinfunction "TOD_19") (pintype "bidirectional"))
      (node (ref "JP5") (pin "2") (pinfunction "2_2") (pintype "passive"))
      (node (ref "R3") (pin "2") (pinfunction "2_2") (pintype "passive"))
    )
    (net (code "85") (name "Net-(IC3A-Y0)") (class "Default")
      (node (ref "IC3") (pin "15") (pinfunction "Y0_15") (pintype "output"))
      (node (ref "JP9") (pin "6") (pinfunction "6_6") (pintype "passive"))
    )
    (net (code "86") (name "Net-(IC3A-Y3)") (class "Default")
      (node (ref "IC3") (pin "12") (pinfunction "Y3_12") (pintype "output"))
      (node (ref "JP9") (pin "4") (pinfunction "4_4") (pintype "passive"))
    )
    (net (code "87") (name "Net-(IC3A-Y5)") (class "Default")
      (node (ref "IC3") (pin "10") (pinfunction "Y5_10") (pintype "output"))
      (node (ref "JP9") (pin "2") (pinfunction "2_2") (pintype "passive"))
    )
    (net (code "88") (name "Net-(IC4A-A)") (class "Default")
      (node (ref "IC4") (pin "1") (pinfunction "A_1") (pintype "input"))
      (node (ref "JP8") (pin "2") (pinfunction "2_2") (pintype "passive"))
    )
    (net (code "89") (name "Net-(IC4A-G2A)") (class "Default")
      (node (ref "IC4") (pin "4") (pinfunction "G2A_4") (pintype "input"))
      (node (ref "JP9") (pin "1") (pinfunction "1_1") (pintype "passive"))
      (node (ref "JP9") (pin "3") (pinfunction "3_3") (pintype "passive"))
      (node (ref "JP9") (pin "5") (pinfunction "5_5") (pintype "passive"))
      (node (ref "JP9") (pin "7") (pinfunction "7_7") (pintype "passive"))
    )
    (net (code "90") (name "Net-(IC5A-Y0)") (class "Default")
      (node (ref "IC5") (pin "4") (pinfunction "Y0_4") (pintype "output"))
      (node (ref "IC9") (pin "1") (pinfunction "I0_1") (pintype "input"))
    )
    (net (code "91") (name "Net-(IC5A-Y1)") (class "Default")
      (node (ref "IC5") (pin "15") (pinfunction "G_15") (pintype "input"))
      (node (ref "IC5") (pin "5") (pinfunction "Y1_5") (pintype "output"))
    )
    (net (code "92") (name "Net-(IC6A-I0)") (class "Default")
      (node (ref "IC6") (pin "1") (pinfunction "I0_1") (pintype "input"))
      (node (ref "IC9") (pin "8") (pinfunction "O_8") (pintype "output"))
    )
    (net (code "93") (name "Net-(IC8A-Q2)") (class "Default")
      (node (ref "IC8") (pin "5") (pinfunction "Q2_5") (pintype "input"))
      (node (ref "JP1") (pin "2") (pinfunction "2_2") (pintype "passive"))
    )
    (net (code "94") (name "Net-(IC9D-O)") (class "Default")
      (node (ref "IC9") (pin "11") (pinfunction "O_11") (pintype "output"))
      (node (ref "JP7") (pin "1") (pinfunction "1_1") (pintype "passive"))
    )
    (net (code "95") (name "Net-(IC10A-O)") (class "Default")
      (node (ref "IC10") (pin "2") (pinfunction "O_2") (pintype "open_collector"))
      (node (ref "R9") (pin "1") (pinfunction "1_1") (pintype "passive"))
    )
    (net (code "96") (name "Net-(IC10B-O)") (class "Default")
      (node (ref "IC10") (pin "4") (pinfunction "O_4") (pintype "open_collector"))
      (node (ref "RN1") (pin "8") (pinfunction "1_8") (pintype "passive"))
    )
    (net (code "97") (name "Net-(IC10C-O)") (class "Default")
      (node (ref "IC10") (pin "6") (pinfunction "O_6") (pintype "open_collector"))
      (node (ref "RN1") (pin "6") (pinfunction "1_6") (pintype "passive"))
    )
    (net (code "98") (name "Net-(IC10D-O)") (class "Default")
      (node (ref "IC10") (pin "8") (pinfunction "O_8") (pintype "open_collector"))
      (node (ref "RN1") (pin "5") (pinfunction "1_5") (pintype "passive"))
    )
    (net (code "99") (name "Net-(IC10E-O)") (class "Default")
      (node (ref "IC10") (pin "10") (pinfunction "O_10") (pintype "open_collector"))
      (node (ref "RN1") (pin "2") (pinfunction "1_2") (pintype "passive"))
    )
    (net (code "100") (name "Net-(IC10F-O)") (class "Default")
      (node (ref "IC10") (pin "12") (pinfunction "O_12") (pintype "open_collector"))
      (node (ref "RN1") (pin "4") (pinfunction "1_4") (pintype "passive"))
    )
    (net (code "101") (name "Net-(IC11A-A)") (class "Default")
      (node (ref "IC11") (pin "10") (pinfunction "A_10") (pintype "input"))
      (node (ref "IC12") (pin "5") (pinfunction "I1_5") (pintype "input"))
      (node (ref "JP2") (pin "2") (pinfunction "2_2") (pintype "passive"))
    )
    (net (code "102") (name "Net-(IC11A-QA)") (class "Default")
      (node (ref "IC11") (pin "9") (pinfunction "QA_9") (pintype "output"))
      (node (ref "IC12") (pin "10") (pinfunction "I1_10") (pintype "input"))
    )
    (net (code "103") (name "Net-(IC12A-I0)") (class "Default")
      (node (ref "IC12") (pin "1") (pinfunction "I0_1") (pintype "input"))
      (node (ref "IC12") (pin "2") (pinfunction "I1_2") (pintype "input"))
      (node (ref "IC12") (pin "4") (pinfunction "I0_4") (pintype "input"))
      (node (ref "IC13") (pin "5") (pinfunction "I_5") (pintype "input"))
      (node (ref "JP6") (pin "2") (pinfunction "2_2") (pintype "passive"))
    )
    (net (code "104") (name "Net-(IC12A-O)") (class "Default")
      (node (ref "IC12") (pin "3") (pinfunction "O_3") (pintype "output"))
      (node (ref "IC12") (pin "9") (pinfunction "I0_9") (pintype "input"))
    )
    (net (code "105") (name "Net-(IC12B-O)") (class "Default")
      (node (ref "IC12") (pin "12") (pinfunction "I0_12") (pintype "input"))
      (node (ref "IC12") (pin "6") (pinfunction "O_6") (pintype "output"))
    )
    (net (code "106") (name "Net-(IC12C-O)") (class "Default")
      (node (ref "IC12") (pin "13") (pinfunction "I1_13") (pintype "input"))
      (node (ref "IC12") (pin "8") (pinfunction "O_8") (pintype "output"))
    )
    (net (code "107") (name "Net-(IC12D-O)") (class "Default")
      (node (ref "IC1") (pin "18") (pinfunction "CLK_18") (pintype "bidirectional"))
      (node (ref "IC12") (pin "11") (pinfunction "O_11") (pintype "output"))
    )
    (net (code "108") (name "Net-(IC13A-O)") (class "Default")
      (node (ref "IC13") (pin "2") (pinfunction "O_2") (pintype "open_collector"))
      (node (ref "RN1") (pin "3") (pinfunction "1_3") (pintype "passive"))
    )
    (net (code "109") (name "Net-(IC13B-I)") (class "Default")
      (node (ref "IC13") (pin "3") (pinfunction "I_3") (pintype "input"))
      (node (ref "IC16") (pin "9") (pinfunction "Y1_9") (pintype "tri_state"))
      (node (ref "RN3") (pin "7") (pinfunction "7_7") (pintype "passive"))
    )
    (net (code "110") (name "Net-(IC13C-O)") (class "Default")
      (node (ref "IC13") (pin "6") (pinfunction "O_6") (pintype "open_collector"))
      (node (ref "P2") (pin "2") (pinfunction "HIDENS_2") (pintype "input"))
      (node (ref "R11") (pin "1") (pinfunction "1_1") (pintype "passive"))
    )
    (net (code "111") (name "Net-(IC13D-O)") (class "Default")
      (node (ref "IC13") (pin "8") (pinfunction "O_8") (pintype "open_collector"))
      (node (ref "RN1") (pin "1") (pinfunction "1_1") (pintype "passive"))
    )
    (net (code "112") (name "Net-(IC13F-I)") (class "Default")
      (node (ref "IC13") (pin "13") (pinfunction "I_13") (pintype "input"))
      (node (ref "IC16") (pin "3") (pinfunction "Y4_3") (pintype "tri_state"))
      (node (ref "RN3") (pin "8") (pinfunction "8_8") (pintype "passive"))
    )
    (net (code "113") (name "Net-(IC14A-O)") (class "Default")
      (node (ref "IC14") (pin "2") (pinfunction "O_2") (pintype "open_collector"))
      (node (ref "R2") (pin "1") (pinfunction "1_1") (pintype "passive"))
    )
    (net (code "114") (name "Net-(IC14B-O)") (class "Default")
      (node (ref "IC14") (pin "4") (pinfunction "O_4") (pintype "open_collector"))
      (node (ref "R1") (pin "1") (pinfunction "1_1") (pintype "passive"))
    )
    (net (code "115") (name "Net-(IC14C-I)") (class "Default")
      (node (ref "IC14") (pin "5") (pinfunction "I_5") (pintype "input"))
      (node (ref "IC6") (pin "6") (pinfunction "O_6") (pintype "output"))
    )
    (net (code "116") (name "Net-(IC15D-O)") (class "Default")
      (node (ref "IC15") (pin "2") (pinfunction "O_2") (pintype "output"))
      (node (ref "IC2") (pin "24") (pinfunction "FLAG_24") (pintype "bidirectional"))
    )
    (net (code "117") (name "Net-(IC15E-I)") (class "Default")
      (node (ref "IC15") (pin "3") (pinfunction "I_3") (pintype "input"))
      (node (ref "IC5") (pin "1") (pinfunction "G_1") (pintype "input"))
      (node (ref "IC8") (pin "19") (pinfunction "P=Q_19") (pintype "output"))
    )
    (net (code "118") (name "Net-(IC15E-O)") (class "Default")
      (node (ref "IC15") (pin "4") (pinfunction "O_4") (pintype "output"))
      (node (ref "IC9") (pin "10") (pinfunction "I1_10") (pintype "input"))
    )
    (net (code "119") (name "Net-(IC15F-O)") (class "Default")
      (node (ref "IC15") (pin "6") (pinfunction "O_6") (pintype "output"))
      (node (ref "JP2") (pin "1") (pinfunction "1_1") (pintype "passive"))
    )
    (net (code "120") (name "Net-(IC18A-A1)") (class "Default")
      (node (ref "IC1") (pin "12") (pinfunction "D7_12") (pintype "bidirectional"))
      (node (ref "IC18") (pin "2") (pinfunction "A1_2") (pintype "bidirectional"))
    )
    (net (code "121") (name "Net-(IC18A-A2)") (class "Default")
      (node (ref "IC1") (pin "11") (pinfunction "D6_11") (pintype "bidirectional"))
      (node (ref "IC18") (pin "3") (pinfunction "A2_3") (pintype "bidirectional"))
    )
    (net (code "122") (name "Net-(IC18A-A3)") (class "Default")
      (node (ref "IC1") (pin "10") (pinfunction "D5_10") (pintype "bidirectional"))
      (node (ref "IC18") (pin "4") (pinfunction "A3_4") (pintype "bidirectional"))
    )
    (net (code "123") (name "Net-(IC18A-A4)") (class "Default")
      (node (ref "IC1") (pin "9") (pinfunction "D4_9") (pintype "bidirectional"))
      (node (ref "IC18") (pin "5") (pinfunction "A4_5") (pintype "bidirectional"))
    )
    (net (code "124") (name "Net-(IC18A-A5)") (class "Default")
      (node (ref "IC1") (pin "8") (pinfunction "D3_8") (pintype "bidirectional"))
      (node (ref "IC18") (pin "6") (pinfunction "A5_6") (pintype "bidirectional"))
    )
    (net (code "125") (name "Net-(IC18A-A6)") (class "Default")
      (node (ref "IC1") (pin "7") (pinfunction "D2_7") (pintype "bidirectional"))
      (node (ref "IC18") (pin "7") (pinfunction "A6_7") (pintype "bidirectional"))
    )
    (net (code "126") (name "Net-(IC18A-A7)") (class "Default")
      (node (ref "IC1") (pin "6") (pinfunction "D1_6") (pintype "bidirectional"))
      (node (ref "IC18") (pin "8") (pinfunction "A7_8") (pintype "bidirectional"))
    )
    (net (code "127") (name "Net-(IC18A-A8)") (class "Default")
      (node (ref "IC1") (pin "5") (pinfunction "D0_5") (pintype "bidirectional"))
      (node (ref "IC18") (pin "9") (pinfunction "A8_9") (pintype "bidirectional"))
    )
    (net (code "128") (name "Net-(IC18A-G)") (class "Default")
      (node (ref "IC1") (pin "1") (pinfunction "/CS_1") (pintype "bidirectional"))
      (node (ref "IC18") (pin "19") (pinfunction "G_19") (pintype "input"))
      (node (ref "IC9") (pin "6") (pinfunction "O_6") (pintype "output"))
    )
    (net (code "129") (name "Net-(JP4-Pad2)") (class "Default")
      (node (ref "JP4") (pin "2") (pinfunction "2_2") (pintype "passive"))
      (node (ref "RN3") (pin "4") (pinfunction "4_4") (pintype "passive"))
      (node (ref "X1") (pin "6") (pinfunction "6_6") (pintype "passive"))
    )
    (net (code "130") (name "Net-(LED1-C)") (class "Default")
      (node (ref "LED1") (pin "K") (pinfunction "C_K") (pintype "passive"))
      (node (ref "R1") (pin "2") (pinfunction "2_2") (pintype "passive"))
    )
    (net (code "131") (name "Net-(LED2-C)") (class "Default")
      (node (ref "LED2") (pin "K") (pinfunction "C_K") (pintype "passive"))
      (node (ref "R2") (pin "2") (pinfunction "2_2") (pintype "passive"))
    )
    (net (code "132") (name "Net-(P2-DIR)") (class "Default")
      (node (ref "P2") (pin "18") (pinfunction "DIR_18") (pintype "input"))
      (node (ref "RN1") (pin "9") (pinfunction "2_9") (pintype "passive"))
    )
    (net (code "133") (name "Net-(P2-DSEL0{slash}MTRB)") (class "Default")
      (node (ref "P2") (pin "10") (pinfunction "DSEL0/MTRB_10") (pintype "input"))
      (node (ref "RN1") (pin "15") (pinfunction "2_15") (pintype "passive"))
    )
    (net (code "134") (name "Net-(P2-DSEL1{slash}SELA)") (class "Default")
      (node (ref "P2") (pin "12") (pinfunction "DSEL1/SELA_12") (pintype "input"))
      (node (ref "RN1") (pin "14") (pinfunction "2_14") (pintype "passive"))
    )
    (net (code "135") (name "Net-(P2-DSEL2{slash}SELB)") (class "Default")
      (node (ref "P2") (pin "14") (pinfunction "DSEL2/SELB_14") (pintype "input"))
      (node (ref "RN1") (pin "13") (pinfunction "2_13") (pintype "passive"))
    )
    (net (code "136") (name "Net-(P2-HEADLOAD)") (class "Default")
      (node (ref "JP10") (pin "2") (pinfunction "2_2") (pintype "passive"))
      (node (ref "P2") (pin "4") (pinfunction "HEADLOAD_4") (pintype "input"))
    )
    (net (code "137") (name "Net-(P2-MOTORON{slash}MTRA)") (class "Default")
      (node (ref "JP10") (pin "1") (pinfunction "1_1") (pintype "passive"))
      (node (ref "P2") (pin "16") (pinfunction "MOTORON/MTRA_16") (pintype "input"))
      (node (ref "RN1") (pin "10") (pinfunction "2_10") (pintype "passive"))
    )
    (net (code "138") (name "Net-(P2-SIDESEL)") (class "Default")
      (node (ref "P2") (pin "32") (pinfunction "SIDESEL_32") (pintype "input"))
      (node (ref "RN1") (pin "16") (pinfunction "2_16") (pintype "passive"))
    )
    (net (code "139") (name "Net-(P2-STEP)") (class "Default")
      (node (ref "P2") (pin "20") (pinfunction "STEP_20") (pintype "input"))
      (node (ref "R9") (pin "2") (pinfunction "2_2") (pintype "passive"))
    )
    (net (code "140") (name "Net-(P2-WRDATA)") (class "Default")
      (node (ref "P2") (pin "22") (pinfunction "WRDATA_22") (pintype "input"))
      (node (ref "RN1") (pin "12") (pinfunction "2_12") (pintype "passive"))
    )
    (net (code "141") (name "Net-(P2-WRGATE)") (class "Default")
      (node (ref "P2") (pin "24") (pinfunction "WRGATE_24") (pintype "input"))
      (node (ref "RN1") (pin "11") (pinfunction "2_11") (pintype "passive"))
    )
    (net (code "142") (name "Net-(QG1-OUT)") (class "Default")
      (node (ref "JP2") (pin "3") (pinfunction "3_3") (pintype "passive"))
      (node (ref "QG1") (pin "8") (pinfunction "OUT_8") (pintype "output"))
    )
    (net (code "143") (name "VCC") (class "Default")
      (node (ref "C1") (pin "+") (pinfunction "+_+") (pintype "passive"))
      (node (ref "C10") (pin "2") (pinfunction "2_2") (pintype "passive"))
      (node (ref "C11") (pin "2") (pinfunction "2_2") (pintype "passive"))
      (node (ref "C12") (pin "2") (pinfunction "2_2") (pintype "passive"))
      (node (ref "C13") (pin "2") (pinfunction "2_2") (pintype "passive"))
      (node (ref "C14") (pin "2") (pinfunction "2_2") (pintype "passive"))
      (node (ref "C15") (pin "2") (pinfunction "2_2") (pintype "passive"))
      (node (ref "C16") (pin "2") (pinfunction "2_2") (pintype "passive"))
      (node (ref "C17") (pin "2") (pinfunction "2_2") (pintype "passive"))
      (node (ref "C19") (pin "2") (pinfunction "2_2") (pintype "passive"))
      (node (ref "C2") (pin "1") (pinfunction "1_1") (pintype "passive"))
      (node (ref "C20") (pin "2") (pinfunction "2_2") (pintype "passive"))
      (node (ref "C21") (pin "2") (pinfunction "2_2") (pintype "passive"))
      (node (ref "C3") (pin "1") (pinfunction "1_1") (pintype "passive"))
      (node (ref "C4") (pin "1") (pinfunction "1_1") (pintype "passive"))
      (node (ref "C5") (pin "1") (pinfunction "1_1") (pintype "passive"))
      (node (ref "C6") (pin "1") (pinfunction "1_1") (pintype "passive"))
      (node (ref "C7") (pin "1") (pinfunction "1_1") (pintype "passive"))
      (node (ref "C8") (pin "1") (pinfunction "1_1") (pintype "passive"))
      (node (ref "C9") (pin "1") (pinfunction "1_1") (pintype "passive"))
      (node (ref "IC3") (pin "6") (pinfunction "G1_6") (pintype "input"))
      (node (ref "IC4") (pin "6") (pinfunction "G1_6") (pintype "input"))
      (node (ref "IC7") (pin "1") (pinfunction "DIR_1") (pintype "input"))
      (node (ref "IC8") (pin "12") (pinfunction "Q7_12") (pintype "input"))
      (node (ref "IC8") (pin "16") (pinfunction "Q3_16") (pintype "input"))
      (node (ref "IC8") (pin "18") (pinfunction "Q1_18") (pintype "input"))
      (node (ref "IC8") (pin "2") (pinfunction "P0_2") (pintype "input"))
      (node (ref "IC8") (pin "3") (pinfunction "Q0_3") (pintype "input"))
      (node (ref "JP1") (pin "3") (pinfunction "3_3") (pintype "passive"))
      (node (ref "JP9") (pin "8") (pinfunction "8_8") (pintype "passive"))
      (node (ref "LED1") (pin "A") (pinfunction "A_A") (pintype "passive"))
      (node (ref "LED2") (pin "A") (pinfunction "A_A") (pintype "passive"))
      (node (ref "P1") (pin "C2") (pinfunction "VCC_C2") (pintype "bidirectional"))
      (node (ref "P1") (pin "C3") (pinfunction "VCC2_C3") (pintype "bidirectional"))
      (node (ref "QG1") (pin "14") (pinfunction "VDD_14") (pintype "power_in"))
      (node (ref "R11") (pin "2") (pinfunction "2_2") (pintype "passive"))
      (node (ref "R3") (pin "1") (pinfunction "1_1") (pintype "passive"))
      (node (ref "R4") (pin "2") (pinfunction "2_2") (pintype "passive"))
      (node (ref "R5") (pin "2") (pinfunction "2_2") (pintype "passive"))
      (node (ref "R6") (pin "2") (pinfunction "2_2") (pintype "passive"))
      (node (ref "R7") (pin "2") (pinfunction "2_2") (pintype "passive"))
      (node (ref "R8") (pin "2") (pinfunction "2_2") (pintype "passive"))
      (node (ref "RN3") (pin "1") (pinfunction "1_1") (pintype "passive"))
    )
    (net (code "144") (name "unconnected-(IC1A-MO-Pad20)") (class "Default")
      (node (ref "IC1") (pin "20") (pinfunction "MO_20") (pintype "bidirectional"))
    )
    (net (code "145") (name "unconnected-(IC2A-PC-Pad18)") (class "Default")
      (node (ref "IC2") (pin "18") (pinfunction "PC_18") (pintype "bidirectional"))
    )
    (net (code "146") (name "unconnected-(IC3A-Y1-Pad14)") (class "Default")
      (node (ref "IC3") (pin "14") (pinfunction "Y1_14") (pintype "output"))
    )
    (net (code "147") (name "unconnected-(IC3A-Y2-Pad13)") (class "Default")
      (node (ref "IC3") (pin "13") (pinfunction "Y2_13") (pintype "output"))
    )
    (net (code "148") (name "unconnected-(IC3A-Y4-Pad11)") (class "Default")
      (node (ref "IC3") (pin "11") (pinfunction "Y4_11") (pintype "output"))
    )
    (net (code "149") (name "unconnected-(IC3A-Y6-Pad9)") (class "Default")
      (node (ref "IC3") (pin "9") (pinfunction "Y6_9") (pintype "output"))
    )
    (net (code "150") (name "unconnected-(IC3A-Y7-Pad7)") (class "Default")
      (node (ref "IC3") (pin "7") (pinfunction "Y7_7") (pintype "output"))
    )
    (net (code "151") (name "unconnected-(IC4A-Y0-Pad15)") (class "Default")
      (node (ref "IC4") (pin "15") (pinfunction "Y0_15") (pintype "output"))
    )
    (net (code "152") (name "unconnected-(IC4A-Y1-Pad14)") (class "Default")
      (node (ref "IC4") (pin "14") (pinfunction "Y1_14") (pintype "output"))
    )
    (net (code "153") (name "unconnected-(IC4A-Y2-Pad13)") (class "Default")
      (node (ref "IC4") (pin "13") (pinfunction "Y2_13") (pintype "output"))
    )
    (net (code "154") (name "unconnected-(IC4A-Y3-Pad12)") (class "Default")
      (node (ref "IC4") (pin "12") (pinfunction "Y3_12") (pintype "output"))
    )
    (net (code "155") (name "unconnected-(IC4A-Y5-Pad10)") (class "Default")
      (node (ref "IC4") (pin "10") (pinfunction "Y5_10") (pintype "output"))
    )
    (net (code "156") (name "unconnected-(IC4A-Y7-Pad7)") (class "Default")
      (node (ref "IC4") (pin "7") (pinfunction "Y7_7") (pintype "output"))
    )
    (net (code "157") (name "unconnected-(IC5A-Y2-Pad6)") (class "Default")
      (node (ref "IC5") (pin "6") (pinfunction "Y2_6") (pintype "output"))
    )
    (net (code "158") (name "unconnected-(IC5A-Y3-Pad7)") (class "Default")
      (node (ref "IC5") (pin "7") (pinfunction "Y3_7") (pintype "output"))
    )
    (net (code "159") (name "unconnected-(IC5B-Y0-Pad12)") (class "Default")
      (node (ref "IC5") (pin "12") (pinfunction "Y0_12") (pintype "output"))
    )
    (net (code "160") (name "unconnected-(IC5B-Y1-Pad11)") (class "Default")
      (node (ref "IC5") (pin "11") (pinfunction "Y1_11") (pintype "output"))
    )
    (net (code "161") (name "unconnected-(IC11A-QB-Pad5)") (class "Default")
      (node (ref "IC11") (pin "5") (pinfunction "QB_5") (pintype "output"))
    )
    (net (code "162") (name "unconnected-(IC11A-QC-Pad4)") (class "Default")
      (node (ref "IC11") (pin "4") (pinfunction "QC_4") (pintype "output"))
    )
    (net (code "163") (name "unconnected-(IC11A-QD-Pad8)") (class "Default")
      (node (ref "IC11") (pin "8") (pinfunction "QD_8") (pintype "output"))
    )
    (net (code "164") (name "unconnected-(IC16A-Y1-Pad18)") (class "Default")
      (node (ref "IC16") (pin "18") (pinfunction "Y1_18") (pintype "tri_state"))
    )
    (net (code "165") (name "unconnected-(IC16A-Y2-Pad16)") (class "Default")
      (node (ref "IC16") (pin "16") (pinfunction "Y2_16") (pintype "tri_state"))
    )
    (net (code "166") (name "unconnected-(IC16B-Y2-Pad7)") (class "Default")
      (node (ref "IC16") (pin "7") (pinfunction "Y2_7") (pintype "tri_state"))
    )
    (net (code "167") (name "unconnected-(IC16B-Y3-Pad5)") (class "Default")
      (node (ref "IC16") (pin "5") (pinfunction "Y3_5") (pintype "tri_state"))
    )
    (net (code "168") (name "unconnected-(IC17A-Q7-Pad12)") (class "Default")
      (node (ref "IC17") (pin "12") (pinfunction "Q7_12") (pintype "output"))
    )
    (net (code "169") (name "unconnected-(IC17A-Q8-Pad9)") (class "Default")
      (node (ref "IC17") (pin "9") (pinfunction "Q8_9") (pintype "output"))
    )
    (net (code "170") (name "unconnected-(P1-2PHI2-PadC29)") (class "Default")
      (node (ref "P1") (pin "C29") (pinfunction "2PHI2_C29") (pintype "bidirectional"))
    )
    (net (code "171") (name "unconnected-(P1-8PHI2-PadC31)") (class "Default")
      (node (ref "P1") (pin "C31") (pinfunction "8PHI2_C31") (pintype "bidirectional"))
    )
    (net (code "172") (name "unconnected-(P1-I2CSCL-PadA14)") (class "Default")
      (node (ref "P1") (pin "A14") (pinfunction "I2CSCL_A14") (pintype "bidirectional"))
    )
    (net (code "173") (name "unconnected-(P1-I2CSDA-PadA13)") (class "Default")
      (node (ref "P1") (pin "A13") (pinfunction "I2CSDA_A13") (pintype "bidirectional"))
    )
    (net (code "174") (name "unconnected-(P1-NOEXEC-PadA10)") (class "Default")
      (node (ref "P1") (pin "A10") (pinfunction "NOEXEC_A10") (pintype "bidirectional"))
    )
    (net (code "175") (name "unconnected-(P1-NOTMAPD-PadA11)") (class "Default")
      (node (ref "P1") (pin "A11") (pinfunction "NOTMAPD_A11") (pintype "bidirectional"))
    )
    (net (code "176") (name "unconnected-(P1-PHI0-PadC28)") (class "Default")
      (node (ref "P1") (pin "C28") (pinfunction "PHI0_C28") (pintype "bidirectional"))
    )
    (net (code "177") (name "unconnected-(P1-PHI1-PadC27)") (class "Default")
      (node (ref "P1") (pin "C27") (pinfunction "PHI1_C27") (pintype "bidirectional"))
    )
    (net (code "178") (name "unconnected-(P1-RDY-PadA26)") (class "Default")
      (node (ref "P1") (pin "A26") (pinfunction "RDY_A26") (pintype "bidirectional"))
    )
    (net (code "179") (name "unconnected-(P1-SYNC-PadC24)") (class "Default")
      (node (ref "P1") (pin "C24") (pinfunction "SYNC_C24") (pintype "bidirectional"))
    )
    (net (code "180") (name "unconnected-(P1-VBUF-PadA2)") (class "Default")
      (node (ref "P1") (pin "A2") (pinfunction "VBUF_A2") (pintype "bidirectional"))
    )
    (net (code "181") (name "unconnected-(P1-VCC33-PadA9)") (class "Default")
      (node (ref "P1") (pin "A9") (pinfunction "VCC33_A9") (pintype "bidirectional"))
    )
    (net (code "182") (name "unconnected-(P1-WPROT-PadA12)") (class "Default")
      (node (ref "P1") (pin "A12") (pinfunction "WPROT_A12") (pintype "bidirectional"))
    )
    (net (code "183") (name "unconnected-(P1-{slash}BE-PadA8)") (class "Default")
      (node (ref "P1") (pin "A8") (pinfunction "/BE_A8") (pintype "bidirectional"))
    )
    (net (code "184") (name "unconnected-(P1-{slash}EXTIO-PadA5)") (class "Default")
      (node (ref "P1") (pin "A5") (pinfunction "/EXTIO_A5") (pintype "bidirectional"))
    )
    (net (code "185") (name "unconnected-(P1-{slash}IOINH-PadA4)") (class "Default")
      (node (ref "P1") (pin "A4") (pinfunction "/IOINH_A4") (pintype "bidirectional"))
    )
    (net (code "186") (name "unconnected-(P1-{slash}NMI-PadA23)") (class "Default")
      (node (ref "P1") (pin "A23") (pinfunction "/NMI_A23") (pintype "bidirectional"))
    )
    (net (code "187") (name "unconnected-(P1-{slash}SO-PadA25)") (class "Default")
      (node (ref "P1") (pin "A25") (pinfunction "/SO_A25") (pintype "bidirectional"))
    )
    (net (code "188") (name "unconnected-(P2-DSEL3-Pad6)") (class "Default")
      (node (ref "P2") (pin "6") (pinfunction "DSEL3_6") (pintype "input"))
    )
    (net (code "189") (name "unconnected-(QG1-CON-Pad1)") (class "Default")
      (node (ref "QG1") (pin "1") (pinfunction "CON_1") (pintype "input"))
    )
  )
)
